# cerebellar_V1_2.net
KiCad netlist of a schematic drawn in EAGLE
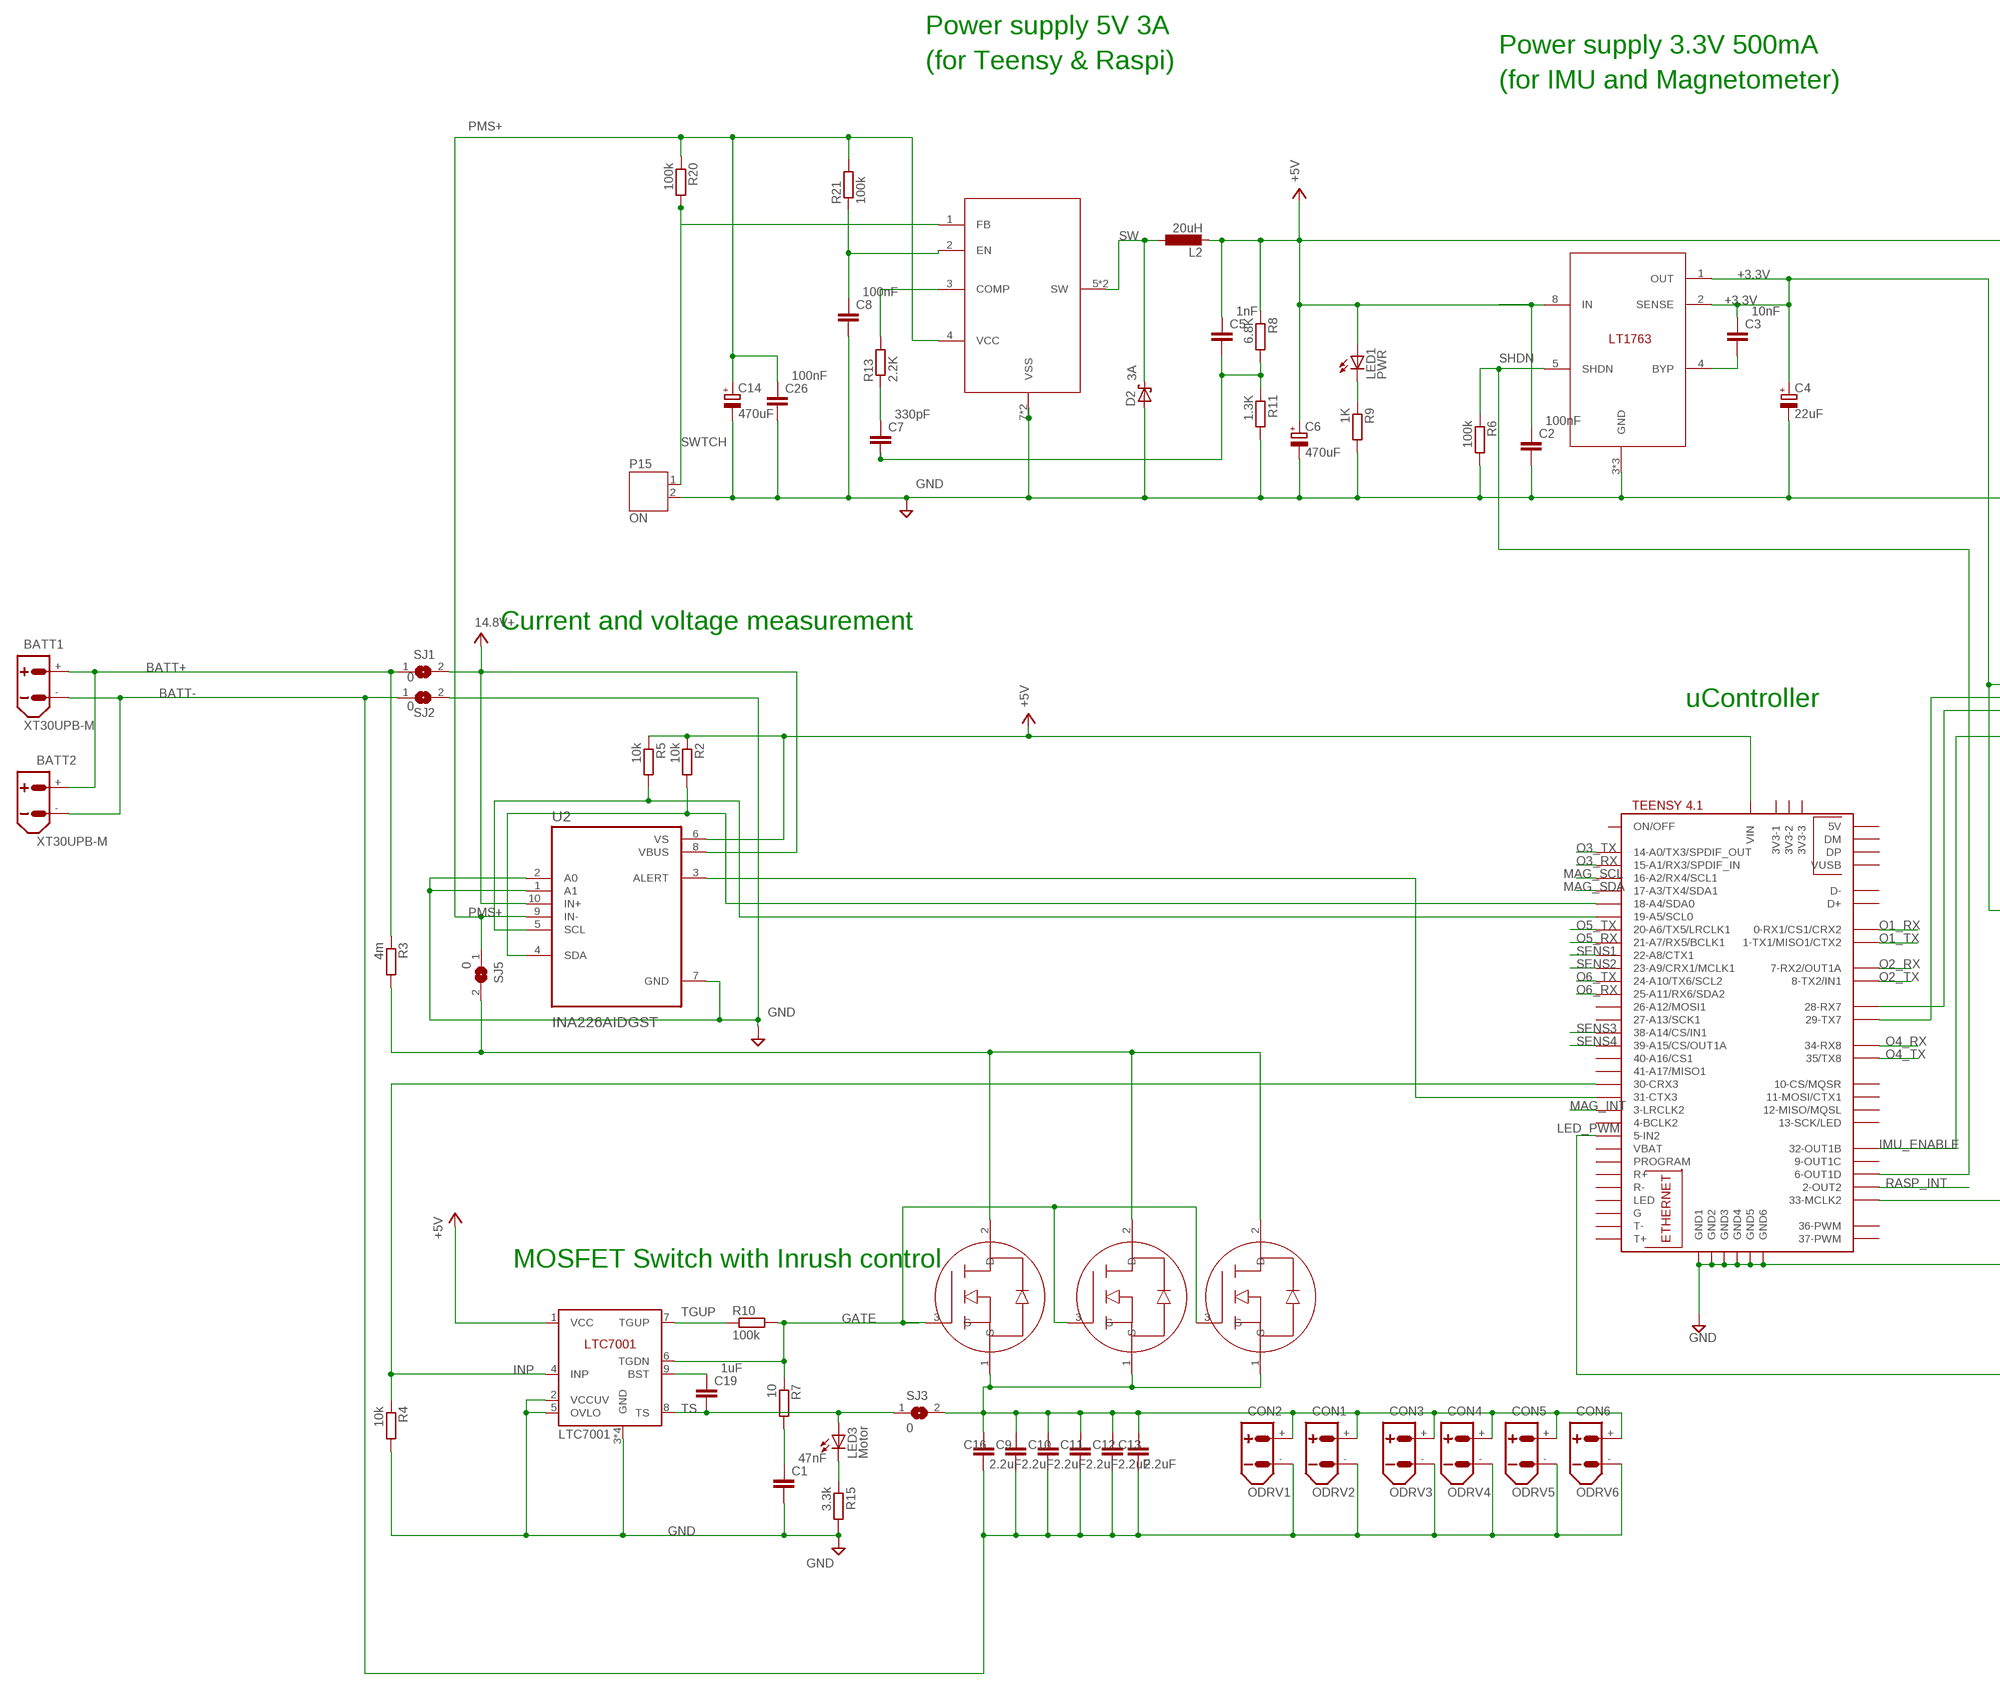
[diagram p0: schematic, sheet 1, part 1 of 2]
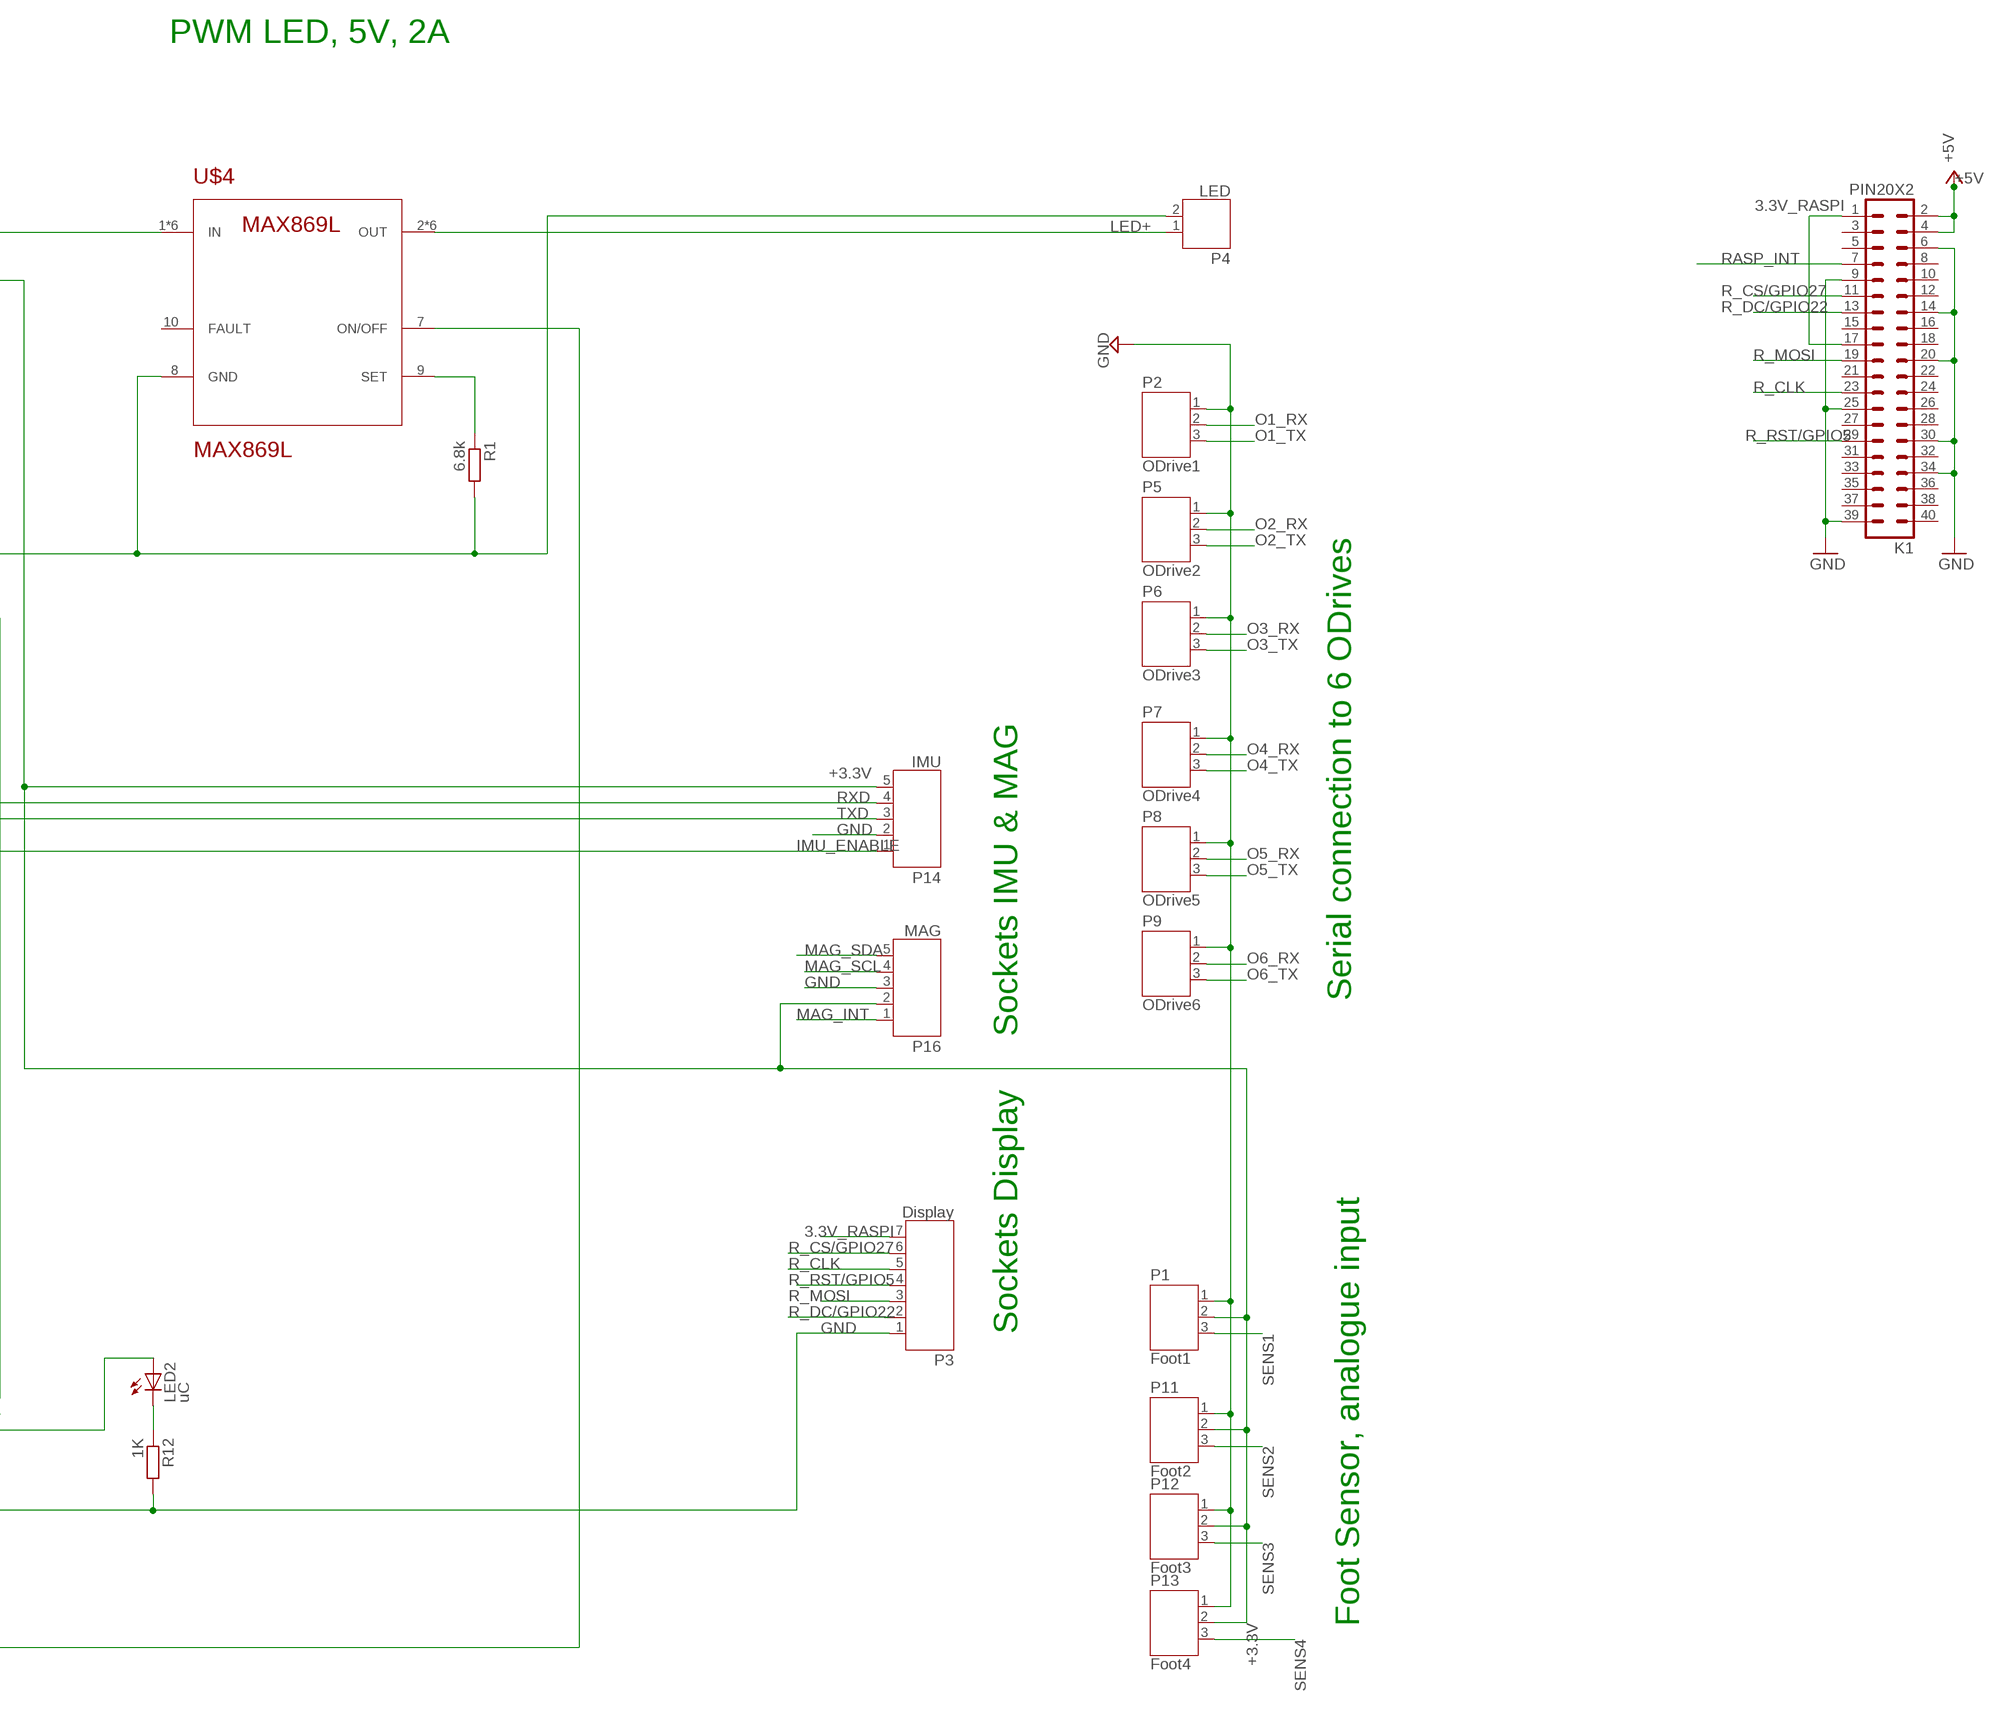
[diagram p1: schematic, sheet 1, part 2 of 2]

(export (version "E")
  (design (tool "Eeschema 10.0.6"))
  (components
    (comp (ref "BATT1")
      (value "XT30UPB-M")
      (footprint "eagle-import:XT30UPB-M")
      (libsource (lib "eagle-import") (part "XT30UPB-M"))
    )
    (comp (ref "BATT2")
      (value "XT30UPB-M")
      (footprint "eagle-import:XT30UPB-M")
      (libsource (lib "eagle-import") (part "XT30UPB-M"))
    )
    (comp (ref "C1")
      (value "47nF")
      (footprint "eagle-import:C050-024X044")
      (libsource (lib "eagle-import") (part "C-EU050-024X044"))
    )
    (comp (ref "C2")
      (value "100nF")
      (footprint "eagle-import:C050-024X044")
      (libsource (lib "eagle-import") (part "C-EU050-024X044"))
    )
    (comp (ref "C3")
      (value "10nF")
      (footprint "eagle-import:C050-024X044")
      (libsource (lib "eagle-import") (part "C-EU050-024X044"))
    )
    (comp (ref "C4")
      (value "22uF")
      (footprint "eagle-import:E2-4")
      (libsource (lib "eagle-import") (part "CPOL-EUE2-4"))
    )
    (comp (ref "C5")
      (value "1nF")
      (footprint "eagle-import:C050-024X044")
      (libsource (lib "eagle-import") (part "C-EU050-024X044"))
    )
    (comp (ref "C6")
      (value "470uF")
      (footprint "eagle-import:E2,5-6")
      (libsource (lib "eagle-import") (part "CPOL-EUE2.5-6"))
    )
    (comp (ref "C7")
      (value "330pF")
      (footprint "eagle-import:C050-024X044")
      (libsource (lib "eagle-import") (part "C-EU050-024X044"))
    )
    (comp (ref "C8")
      (value "100nF")
      (footprint "eagle-import:C050-024X044")
      (libsource (lib "eagle-import") (part "C-EU050-024X044"))
    )
    (comp (ref "C9")
      (value "2.2uF")
      (footprint "eagle-import:C050-024X044")
      (libsource (lib "eagle-import") (part "C-EU050-024X044"))
    )
    (comp (ref "C10")
      (value "2.2uF")
      (footprint "eagle-import:C050-024X044")
      (libsource (lib "eagle-import") (part "C-EU050-024X044"))
    )
    (comp (ref "C11")
      (value "2.2uF")
      (footprint "eagle-import:C050-024X044")
      (libsource (lib "eagle-import") (part "C-EU050-024X044"))
    )
    (comp (ref "C12")
      (value "2.2uF")
      (footprint "eagle-import:C050-024X044")
      (libsource (lib "eagle-import") (part "C-EU050-024X044"))
    )
    (comp (ref "C13")
      (value "2.2uF")
      (footprint "eagle-import:C050-024X044")
      (libsource (lib "eagle-import") (part "C-EU050-024X044"))
    )
    (comp (ref "C14")
      (value "470uF")
      (footprint "eagle-import:E2,5-6")
      (libsource (lib "eagle-import") (part "CPOL-EUE2.5-6"))
    )
    (comp (ref "C16")
      (value "2.2uF")
      (footprint "eagle-import:C050-024X044")
      (libsource (lib "eagle-import") (part "C-EU050-024X044"))
    )
    (comp (ref "C19")
      (value "1uF")
      (footprint "eagle-import:C050-024X044")
      (libsource (lib "eagle-import") (part "C-EU050-024X044"))
    )
    (comp (ref "C26")
      (value "100nF")
      (footprint "eagle-import:C050-024X044")
      (libsource (lib "eagle-import") (part "C-EU050-024X044"))
    )
    (comp (ref "CON1")
      (value "ODRV2")
      (footprint "eagle-import:XT30UPB-F")
      (libsource (lib "eagle-import") (part "XT30UPB-F"))
    )
    (comp (ref "CON2")
      (value "ODRV1")
      (footprint "eagle-import:XT30UPB-F")
      (libsource (lib "eagle-import") (part "XT30UPB-F"))
    )
    (comp (ref "CON3")
      (value "ODRV3")
      (footprint "eagle-import:XT30UPB-F")
      (libsource (lib "eagle-import") (part "XT30UPB-F"))
    )
    (comp (ref "CON4")
      (value "ODRV4")
      (footprint "eagle-import:XT30UPB-F")
      (libsource (lib "eagle-import") (part "XT30UPB-F"))
    )
    (comp (ref "CON5")
      (value "ODRV5")
      (footprint "eagle-import:XT30UPB-F")
      (libsource (lib "eagle-import") (part "XT30UPB-F"))
    )
    (comp (ref "CON6")
      (value "ODRV6")
      (footprint "eagle-import:XT30UPB-F")
      (libsource (lib "eagle-import") (part "XT30UPB-F"))
    )
    (comp (ref "D2")
      (value "3A")
      (footprint "eagle-import:DO41-10")
      (libsource (lib "eagle-import") (part "SCHOTTKY-DIODEDO41"))
    )
    (comp (ref "IC3")
      (value "LTC7001")
      (footprint "eagle-import:MSOP10")
      (fields (field (name "MPN") "AD7992BRMZ-0"))
      (libsource (lib "eagle-import") (part "LTC7001"))
    )
    (comp (ref "K1")
      (value "PIN20X2")
      (footprint "eagle-import:PIN_20X2")
      (libsource (lib "eagle-import") (part "PIN20X2"))
    )
    (comp (ref "L2")
      (value "20uH")
      (footprint "eagle-import:IRF-3")
      (libsource (lib "eagle-import") (part "L-EUIRF-3"))
    )
    (comp (ref "LED1")
      (value "PWR")
      (footprint "eagle-import:LED3MM")
      (libsource (lib "eagle-import") (part "LED3MM"))
    )
    (comp (ref "LED2")
      (value "uC")
      (footprint "eagle-import:LED3MM")
      (libsource (lib "eagle-import") (part "LED3MM"))
    )
    (comp (ref "LED3")
      (value "Motor")
      (footprint "eagle-import:LED3MM")
      (libsource (lib "eagle-import") (part "LED3MM"))
    )
    (comp (ref "P1")
      (value "Foot1")
      (footprint "eagle-import:JST-PH3")
      (libsource (lib "eagle-import") (part "JST-PH3"))
    )
    (comp (ref "P2")
      (value "ODrive1")
      (footprint "eagle-import:JST-PH3")
      (libsource (lib "eagle-import") (part "JST-PH3"))
    )
    (comp (ref "P3")
      (value "Display")
      (footprint "eagle-import:JST-PH7")
      (libsource (lib "eagle-import") (part "JST-PH7"))
    )
    (comp (ref "P4")
      (value "LED")
      (footprint "eagle-import:JST-PH2")
      (libsource (lib "eagle-import") (part "JST-PH2"))
    )
    (comp (ref "P5")
      (value "ODrive2")
      (footprint "eagle-import:JST-PH3")
      (libsource (lib "eagle-import") (part "JST-PH3"))
    )
    (comp (ref "P6")
      (value "ODrive3")
      (footprint "eagle-import:JST-PH3")
      (libsource (lib "eagle-import") (part "JST-PH3"))
    )
    (comp (ref "P7")
      (value "ODrive4")
      (footprint "eagle-import:JST-PH3")
      (libsource (lib "eagle-import") (part "JST-PH3"))
    )
    (comp (ref "P8")
      (value "ODrive5")
      (footprint "eagle-import:JST-PH3")
      (libsource (lib "eagle-import") (part "JST-PH3"))
    )
    (comp (ref "P9")
      (value "ODrive6")
      (footprint "eagle-import:JST-PH3")
      (libsource (lib "eagle-import") (part "JST-PH3"))
    )
    (comp (ref "P11")
      (value "Foot2")
      (footprint "eagle-import:JST-PH3")
      (libsource (lib "eagle-import") (part "JST-PH3"))
    )
    (comp (ref "P12")
      (value "Foot3")
      (footprint "eagle-import:JST-PH3")
      (libsource (lib "eagle-import") (part "JST-PH3"))
    )
    (comp (ref "P13")
      (value "Foot4")
      (footprint "eagle-import:JST-PH3")
      (libsource (lib "eagle-import") (part "JST-PH3"))
    )
    (comp (ref "P14")
      (value "IMU")
      (footprint "eagle-import:JST-PH5")
      (libsource (lib "eagle-import") (part "JST-PH5"))
    )
    (comp (ref "P15")
      (value "ON")
      (footprint "eagle-import:JST-PH2")
      (libsource (lib "eagle-import") (part "JST-PH2"))
    )
    (comp (ref "P16")
      (value "MAG")
      (footprint "eagle-import:JST-PH5")
      (libsource (lib "eagle-import") (part "JST-PH5"))
    )
    (comp (ref "R1")
      (value "6.8k")
      (footprint "eagle-import:0204_7")
      (libsource (lib "eagle-import") (part "R-EU_0204/7"))
    )
    (comp (ref "R2")
      (value "10k")
      (footprint "eagle-import:0204_7")
      (libsource (lib "eagle-import") (part "R-EU_0204/7"))
    )
    (comp (ref "R3")
      (value "4m")
      (footprint "eagle-import:R2512")
      (libsource (lib "eagle-import") (part "R-EU_R2512"))
    )
    (comp (ref "R4")
      (value "10k")
      (footprint "eagle-import:0204_7")
      (libsource (lib "eagle-import") (part "R-EU_0204/7"))
    )
    (comp (ref "R5")
      (value "10k")
      (footprint "eagle-import:0204_7")
      (libsource (lib "eagle-import") (part "R-EU_0204/7"))
    )
    (comp (ref "R6")
      (value "100k")
      (footprint "eagle-import:0204_7")
      (libsource (lib "eagle-import") (part "R-EU_0204/7"))
    )
    (comp (ref "R7")
      (value "10")
      (footprint "eagle-import:0204_7")
      (libsource (lib "eagle-import") (part "R-EU_0204/7"))
    )
    (comp (ref "R8")
      (value "6.8K")
      (footprint "eagle-import:0204_7")
      (libsource (lib "eagle-import") (part "R-EU_0204/7"))
    )
    (comp (ref "R9")
      (value "1K")
      (footprint "eagle-import:0204_7")
      (libsource (lib "eagle-import") (part "R-EU_0204/7"))
    )
    (comp (ref "R10")
      (value "100k")
      (footprint "eagle-import:0204_7")
      (libsource (lib "eagle-import") (part "R-EU_0204/7"))
    )
    (comp (ref "R11")
      (value "1.3K")
      (footprint "eagle-import:0204_7")
      (libsource (lib "eagle-import") (part "R-EU_0204/7"))
    )
    (comp (ref "R12")
      (value "1K")
      (footprint "eagle-import:0204_7")
      (libsource (lib "eagle-import") (part "R-EU_0204/7"))
    )
    (comp (ref "R13")
      (value "2.2K")
      (footprint "eagle-import:0204_7")
      (libsource (lib "eagle-import") (part "R-EU_0204/7"))
    )
    (comp (ref "R15")
      (value "3.3k")
      (footprint "eagle-import:0204_7")
      (libsource (lib "eagle-import") (part "R-EU_0204/7"))
    )
    (comp (ref "R20")
      (value "100k")
      (footprint "eagle-import:0204_7")
      (libsource (lib "eagle-import") (part "R-EU_0204/7"))
    )
    (comp (ref "R21")
      (value "100k")
      (footprint "eagle-import:0204_7")
      (libsource (lib "eagle-import") (part "R-EU_0204/7"))
    )
    (comp (ref "SJ1") (value "0") (footprint "eagle-import:SJ") (libsource (lib "eagle-import") (part "SJ")))
    (comp (ref "SJ2") (value "0") (footprint "eagle-import:SJ") (libsource (lib "eagle-import") (part "SJ")))
    (comp (ref "SJ3") (value "0") (footprint "eagle-import:SJ") (libsource (lib "eagle-import") (part "SJ")))
    (comp (ref "SJ5") (value "0") (footprint "eagle-import:SJ") (libsource (lib "eagle-import") (part "SJ")))
    (comp (ref "U$1")
      (value "TEENSY41")
      (footprint "eagle-import:TEENSY41")
      (libsource (lib "eagle-import") (part "TEENSY41"))
    )
    (comp (ref "U$2")
      (value "IRF2804-BACK")
      (footprint "eagle-import:TO-220H-BACK")
      (libsource (lib "eagle-import") (part "IRF2804-BACK"))
    )
    (comp (ref "U$3")
      (value "IRF2804-BACK")
      (footprint "eagle-import:TO-220H-BACK")
      (libsource (lib "eagle-import") (part "IRF2804-BACK"))
    )
    (comp (ref "U$4")
      (value "MAX869L")
      (footprint "eagle-import:TSSOP-16")
      (libsource (lib "eagle-import") (part "MAX769L"))
    )
    (comp (ref "U$5")
      (value "IRF2804-BACK")
      (footprint "eagle-import:TO-220H-BACK")
      (libsource (lib "eagle-import") (part "IRF2804-BACK"))
    )
    (comp (ref "U$6")
      (value "TS2509")
      (footprint "eagle-import:SO08")
      (libsource (lib "eagle-import") (part "TS2509"))
    )
    (comp (ref "U$8")
      (value "LT1763")
      (footprint "eagle-import:SO08")
      (libsource (lib "eagle-import") (part "LT1763"))
    )
    (comp (ref "U2")
      (value "INA226AIDGST")
      (footprint "eagle-import:SOP50P490X110-10N")
      (fields (field (name "MF") "Texas Instruments"))
      (libsource (lib "eagle-import") (part "INA226AIDGST"))
    )
  )
  (nets
    (net (code "1") (name "+5V") (class "Default")
      (node (ref "C2") (pin "1") (pinfunction "1_1") (pintype "passive"))
      (node (ref "C5") (pin "1") (pinfunction "1_1") (pintype "passive"))
      (node (ref "C6") (pin "+") (pinfunction "+_+") (pintype "passive"))
      (node (ref "IC3") (pin "1") (pinfunction "VCC_1") (pintype "power_in"))
      (node (ref "K1") (pin "2") (pinfunction "2_2") (pintype "passive"))
      (node (ref "K1") (pin "4") (pinfunction "4_4") (pintype "passive"))
      (node (ref "L2") (pin "2") (pinfunction "2_2") (pintype "passive"))
      (node (ref "LED1") (pin "A") (pinfunction "A_A") (pintype "passive"))
      (node (ref "R2") (pin "1") (pinfunction "1_1") (pintype "passive"))
      (node (ref "R5") (pin "1") (pinfunction "1_1") (pintype "passive"))
      (node (ref "R8") (pin "1") (pinfunction "1_1") (pintype "passive"))
      (node (ref "U$1") (pin "VIN") (pinfunction "VIN_VIN") (pintype "bidirectional"))
      (node (ref "U$4") (pin "1") (pinfunction "IN_1") (pintype "bidirectional"))
      (node (ref "U$4") (pin "12") (pinfunction "IN_12") (pintype "bidirectional"))
      (node (ref "U$4") (pin "13") (pinfunction "IN_13") (pintype "bidirectional"))
      (node (ref "U$4") (pin "16") (pinfunction "IN_16") (pintype "bidirectional"))
      (node (ref "U$4") (pin "4") (pinfunction "IN_4") (pintype "bidirectional"))
      (node (ref "U$4") (pin "5") (pinfunction "IN_5") (pintype "bidirectional"))
      (node (ref "U$8") (pin "8") (pinfunction "IN_8") (pintype "input"))
      (node (ref "U2") (pin "6") (pinfunction "VS_6") (pintype "power_in"))
    )
    (net (code "2") (name "/+3.3V") (class "Default")
      (node (ref "C3") (pin "1") (pinfunction "1_1") (pintype "passive"))
      (node (ref "C4") (pin "+") (pinfunction "+_+") (pintype "passive"))
      (node (ref "P1") (pin "2") (pinfunction "2_2") (pintype "passive"))
      (node (ref "P11") (pin "2") (pinfunction "2_2") (pintype "passive"))
      (node (ref "P12") (pin "2") (pinfunction "2_2") (pintype "passive"))
      (node (ref "P13") (pin "2") (pinfunction "2_2") (pintype "passive"))
      (node (ref "P14") (pin "5") (pinfunction "5_5") (pintype "passive"))
      (node (ref "P16") (pin "2") (pinfunction "2_2") (pintype "passive"))
      (node (ref "U$8") (pin "1") (pinfunction "OUT_1") (pintype "output"))
      (node (ref "U$8") (pin "2") (pinfunction "SENSE_2") (pintype "input"))
    )
    (net (code "3") (name "/3.3V_RASPI") (class "Default")
      (node (ref "K1") (pin "1") (pinfunction "1_1") (pintype "passive"))
      (node (ref "K1") (pin "17") (pinfunction "17_17") (pintype "passive"))
      (node (ref "P3") (pin "7") (pinfunction "7_7") (pintype "passive"))
    )
    (net (code "4") (name "/BATT+") (class "Default")
      (node (ref "BATT1") (pin "+") (pinfunction "+_+") (pintype "power_in"))
      (node (ref "BATT2") (pin "+") (pinfunction "+_+") (pintype "power_in"))
      (node (ref "R3") (pin "1") (pinfunction "1_1") (pintype "passive"))
      (node (ref "SJ1") (pin "1") (pinfunction "1_1") (pintype "passive"))
    )
    (net (code "5") (name "/BATT-") (class "Default")
      (node (ref "BATT1") (pin "-") (pinfunction "-_-") (pintype "power_in"))
      (node (ref "BATT2") (pin "-") (pinfunction "-_-") (pintype "power_in"))
      (node (ref "C10") (pin "2") (pinfunction "2_2") (pintype "passive"))
      (node (ref "C11") (pin "2") (pinfunction "2_2") (pintype "passive"))
      (node (ref "C12") (pin "2") (pinfunction "2_2") (pintype "passive"))
      (node (ref "C13") (pin "2") (pinfunction "2_2") (pintype "passive"))
      (node (ref "C16") (pin "2") (pinfunction "2_2") (pintype "passive"))
      (node (ref "C9") (pin "2") (pinfunction "2_2") (pintype "passive"))
      (node (ref "CON1") (pin "-") (pinfunction "-_-") (pintype "power_in"))
      (node (ref "CON2") (pin "-") (pinfunction "-_-") (pintype "power_in"))
      (node (ref "CON3") (pin "-") (pinfunction "-_-") (pintype "power_in"))
      (node (ref "CON4") (pin "-") (pinfunction "-_-") (pintype "power_in"))
      (node (ref "CON5") (pin "-") (pinfunction "-_-") (pintype "power_in"))
      (node (ref "CON6") (pin "-") (pinfunction "-_-") (pintype "power_in"))
      (node (ref "SJ2") (pin "1") (pinfunction "1_1") (pintype "passive"))
    )
    (net (code "6") (name "/GATE") (class "Default")
      (node (ref "IC3") (pin "6") (pinfunction "TGDN_6") (pintype "output"))
      (node (ref "R10") (pin "2") (pinfunction "2_2") (pintype "passive"))
      (node (ref "R7") (pin "1") (pinfunction "1_1") (pintype "passive"))
      (node (ref "U$2") (pin "3") (pinfunction "G_3") (pintype "bidirectional"))
      (node (ref "U$3") (pin "3") (pinfunction "G_3") (pintype "bidirectional"))
      (node (ref "U$5") (pin "3") (pinfunction "G_3") (pintype "bidirectional"))
    )
    (net (code "7") (name "/IMU_ENABLE") (class "Default")
      (node (ref "P14") (pin "1") (pinfunction "1_1") (pintype "passive"))
      (node (ref "U$1") (pin "32-OUT1B") (pinfunction "32-OUT1B_32-OUT1B") (pintype "bidirectional"))
    )
    (net (code "8") (name "/INP") (class "Default")
      (node (ref "IC3") (pin "4") (pinfunction "INP_4") (pintype "input"))
      (node (ref "R4") (pin "1") (pinfunction "1_1") (pintype "passive"))
      (node (ref "U$1") (pin "30-CRX3") (pinfunction "30-CRX3_30-CRX3") (pintype "bidirectional"))
    )
    (net (code "9") (name "/LED+") (class "Default")
      (node (ref "P4") (pin "1") (pinfunction "1_1") (pintype "passive"))
      (node (ref "U$4") (pin "11") (pinfunction "OUT_11") (pintype "bidirectional"))
      (node (ref "U$4") (pin "14") (pinfunction "OUT_14") (pintype "bidirectional"))
      (node (ref "U$4") (pin "15") (pinfunction "OUT_15") (pintype "bidirectional"))
      (node (ref "U$4") (pin "2") (pinfunction "OUT_2") (pintype "bidirectional"))
      (node (ref "U$4") (pin "3") (pinfunction "OUT_3") (pintype "bidirectional"))
      (node (ref "U$4") (pin "6") (pinfunction "OUT_6") (pintype "bidirectional"))
    )
    (net (code "10") (name "/LED_PWM") (class "Default")
      (node (ref "U$1") (pin "5-IN2") (pinfunction "5-IN2_5-IN2") (pintype "bidirectional"))
      (node (ref "U$4") (pin "7") (pinfunction "ON/OFF_7") (pintype "bidirectional"))
    )
    (net (code "11") (name "/MAG_INT") (class "Default")
      (node (ref "P16") (pin "1") (pinfunction "1_1") (pintype "passive"))
      (node (ref "U$1") (pin "3-LRCLK2") (pinfunction "3-LRCLK2_3-LRCLK2") (pintype "bidirectional"))
    )
    (net (code "12") (name "/MAG_SCL") (class "Default")
      (node (ref "P16") (pin "4") (pinfunction "4_4") (pintype "passive"))
      (node (ref "U$1") (pin "16-A2/RX4/SCL1") (pinfunction "16-A2/RX4/SCL1_16-A2/RX4/SCL1") (pintype "bidirectional"))
    )
    (net (code "13") (name "/MAG_SDA") (class "Default")
      (node (ref "P16") (pin "5") (pinfunction "5_5") (pintype "passive"))
      (node (ref "U$1") (pin "17-A3/TX4/SDA1") (pinfunction "17-A3/TX4/SDA1_17-A3/TX4/SDA1") (pintype "bidirectional"))
    )
    (net (code "14") (name "/O1_RX") (class "Default")
      (node (ref "P2") (pin "2") (pinfunction "2_2") (pintype "passive"))
      (node (ref "U$1") (pin "0-RX1/CS1/CRX2") (pinfunction "0-RX1/CS1/CRX2_0-RX1/CS1/CRX2") (pintype "bidirectional"))
    )
    (net (code "15") (name "/O1_TX") (class "Default")
      (node (ref "P2") (pin "3") (pinfunction "3_3") (pintype "passive"))
      (node (ref "U$1") (pin "1-TX1/MISO1/CTX2") (pinfunction "1-TX1/MISO1/CTX2_1-TX1/MISO1/CTX2") (pintype "bidirectional"))
    )
    (net (code "16") (name "/O2_RX") (class "Default")
      (node (ref "P5") (pin "2") (pinfunction "2_2") (pintype "passive"))
      (node (ref "U$1") (pin "7-RX2/OUT1A") (pinfunction "7-RX2/OUT1A_7-RX2/OUT1A") (pintype "bidirectional"))
    )
    (net (code "17") (name "/O2_TX") (class "Default")
      (node (ref "P5") (pin "3") (pinfunction "3_3") (pintype "passive"))
      (node (ref "U$1") (pin "8-TX2/IN1") (pinfunction "8-TX2/IN1_8-TX2/IN1") (pintype "bidirectional"))
    )
    (net (code "18") (name "/O3_RX") (class "Default")
      (node (ref "P6") (pin "2") (pinfunction "2_2") (pintype "passive"))
      (node (ref "U$1") (pin "15-A1/RX3/SPDIF_IN") (pinfunction "15-A1/RX3/SPDIF_IN_15-A1/RX3/SPDIF_IN") (pintype "bidirectional"))
    )
    (net (code "19") (name "/O3_TX") (class "Default")
      (node (ref "P6") (pin "3") (pinfunction "3_3") (pintype "passive"))
      (node (ref "U$1") (pin "14-A0/TX3/SPDIF_OUT") (pinfunction "14-A0/TX3/SPDIF_OUT_14-A0/TX3/SPDIF_OUT") (pintype "bidirectional"))
    )
    (net (code "20") (name "/O4_RX") (class "Default")
      (node (ref "P7") (pin "2") (pinfunction "2_2") (pintype "passive"))
      (node (ref "U$1") (pin "34-RX8") (pinfunction "34-RX8_34-RX8") (pintype "bidirectional"))
    )
    (net (code "21") (name "/O4_TX") (class "Default")
      (node (ref "P7") (pin "3") (pinfunction "3_3") (pintype "passive"))
      (node (ref "U$1") (pin "35-TX8") (pinfunction "35/TX8_35-TX8") (pintype "bidirectional"))
    )
    (net (code "22") (name "/O5_RX") (class "Default")
      (node (ref "P8") (pin "2") (pinfunction "2_2") (pintype "passive"))
      (node (ref "U$1") (pin "21-A7/RX5/BCLK1") (pinfunction "21-A7/RX5/BCLK1_21-A7/RX5/BCLK1") (pintype "bidirectional"))
    )
    (net (code "23") (name "/O5_TX") (class "Default")
      (node (ref "P8") (pin "3") (pinfunction "3_3") (pintype "passive"))
      (node (ref "U$1") (pin "20-A6/TX5/LRCLK1") (pinfunction "20-A6/TX5/LRCLK1_20-A6/TX5/LRCLK1") (pintype "bidirectional"))
    )
    (net (code "24") (name "/O6_RX") (class "Default")
      (node (ref "P9") (pin "2") (pinfunction "2_2") (pintype "passive"))
      (node (ref "U$1") (pin "25-A11/RX6/SDA2") (pinfunction "25-A11/RX6/SDA2_25-A11/RX6/SDA2") (pintype "bidirectional"))
    )
    (net (code "25") (name "/O6_TX") (class "Default")
      (node (ref "P9") (pin "3") (pinfunction "3_3") (pintype "passive"))
      (node (ref "U$1") (pin "24-A10/TX6/SCL2") (pinfunction "24-A10/TX6/SCL2_24-A10/TX6/SCL2") (pintype "bidirectional"))
    )
    (net (code "26") (name "/PMS+") (class "Default")
      (node (ref "C14") (pin "+") (pinfunction "+_+") (pintype "passive"))
      (node (ref "C26") (pin "1") (pinfunction "1_1") (pintype "passive"))
      (node (ref "R20") (pin "1") (pinfunction "1_1") (pintype "passive"))
      (node (ref "R21") (pin "2") (pinfunction "2_2") (pintype "passive"))
      (node (ref "SJ5") (pin "1") (pinfunction "1_1") (pintype "passive"))
      (node (ref "U$6") (pin "4") (pinfunction "VCC_4") (pintype "input"))
      (node (ref "U2") (pin "9") (pinfunction "IN-_9") (pintype "input"))
    )
    (net (code "27") (name "/RASP_INT") (class "Default")
      (node (ref "K1") (pin "7") (pinfunction "7_7") (pintype "passive"))
      (node (ref "U$1") (pin "2-OUT2") (pinfunction "2-OUT2_2-OUT2") (pintype "bidirectional"))
    )
    (net (code "28") (name "/RXD") (class "Default")
      (node (ref "P14") (pin "4") (pinfunction "4_4") (pintype "passive"))
      (node (ref "U$1") (pin "29-TX7") (pinfunction "29-TX7_29-TX7") (pintype "bidirectional"))
    )
    (net (code "29") (name "/R_CLK") (class "Default")
      (node (ref "K1") (pin "23") (pinfunction "23_23") (pintype "passive"))
      (node (ref "P3") (pin "5") (pinfunction "5_5") (pintype "passive"))
    )
    (net (code "30") (name "/R_CS{slash}GPIO27") (class "Default")
      (node (ref "K1") (pin "11") (pinfunction "11_11") (pintype "passive"))
      (node (ref "P3") (pin "6") (pinfunction "6_6") (pintype "passive"))
    )
    (net (code "31") (name "/R_DC{slash}GPIO22") (class "Default")
      (node (ref "K1") (pin "13") (pinfunction "13_13") (pintype "passive"))
      (node (ref "P3") (pin "2") (pinfunction "2_2") (pintype "passive"))
    )
    (net (code "32") (name "/R_MOSI") (class "Default")
      (node (ref "K1") (pin "19") (pinfunction "19_19") (pintype "passive"))
      (node (ref "P3") (pin "3") (pinfunction "3_3") (pintype "passive"))
    )
    (net (code "33") (name "/R_RST{slash}GPIO5") (class "Default")
      (node (ref "K1") (pin "29") (pinfunction "29_29") (pintype "passive"))
      (node (ref "P3") (pin "4") (pinfunction "4_4") (pintype "passive"))
    )
    (net (code "34") (name "/SENS1") (class "Default")
      (node (ref "P1") (pin "3") (pinfunction "3_3") (pintype "passive"))
      (node (ref "U$1") (pin "22-A8/CTX1") (pinfunction "22-A8/CTX1_22-A8/CTX1") (pintype "bidirectional"))
    )
    (net (code "35") (name "/SENS2") (class "Default")
      (node (ref "P11") (pin "3") (pinfunction "3_3") (pintype "passive"))
      (node (ref "U$1") (pin "23-A9/CRX1/MCLK1") (pinfunction "23-A9/CRX1/MCLK1_23-A9/CRX1/MCLK1") (pintype "bidirectional"))
    )
    (net (code "36") (name "/SENS3") (class "Default")
      (node (ref "P12") (pin "3") (pinfunction "3_3") (pintype "passive"))
      (node (ref "U$1") (pin "38-A14/CS/IN1") (pinfunction "38-A14/CS/IN1_38-A14/CS/IN1") (pintype "bidirectional"))
    )
    (net (code "37") (name "/SENS4") (class "Default")
      (node (ref "P13") (pin "3") (pinfunction "3_3") (pintype "passive"))
      (node (ref "U$1") (pin "39-A15/CS/OUT1A") (pinfunction "39-A15/CS/OUT1A_39-A15/CS/OUT1A") (pintype "bidirectional"))
    )
    (net (code "38") (name "/SHDN") (class "Default")
      (node (ref "R6") (pin "1") (pinfunction "1_1") (pintype "passive"))
      (node (ref "U$1") (pin "6-OUT1D") (pinfunction "6-OUT1D_6-OUT1D") (pintype "bidirectional"))
      (node (ref "U$8") (pin "5") (pinfunction "SHDN_5") (pintype "bidirectional"))
    )
    (net (code "39") (name "/SW") (class "Default")
      (node (ref "D2") (pin "C") (pinfunction "C_C") (pintype "passive"))
      (node (ref "L2") (pin "1") (pinfunction "1_1") (pintype "passive"))
      (node (ref "U$6") (pin "5") (pinfunction "SW_5") (pintype "output"))
      (node (ref "U$6") (pin "6") (pinfunction "SW_6") (pintype "output"))
    )
    (net (code "40") (name "/SWTCH") (class "Default")
      (node (ref "P15") (pin "1") (pinfunction "1_1") (pintype "passive"))
      (node (ref "R20") (pin "2") (pinfunction "2_2") (pintype "passive"))
      (node (ref "U$6") (pin "1") (pinfunction "FB_1") (pintype "bidirectional"))
    )
    (net (code "41") (name "/TGUP") (class "Default")
      (node (ref "IC3") (pin "7") (pinfunction "TGUP_7") (pintype "input"))
      (node (ref "R10") (pin "1") (pinfunction "1_1") (pintype "passive"))
    )
    (net (code "42") (name "/TS") (class "Default")
      (node (ref "C19") (pin "2") (pinfunction "2_2") (pintype "passive"))
      (node (ref "IC3") (pin "8") (pinfunction "TS_8") (pintype "bidirectional"))
      (node (ref "LED3") (pin "A") (pinfunction "A_A") (pintype "passive"))
      (node (ref "SJ3") (pin "1") (pinfunction "1_1") (pintype "passive"))
    )
    (net (code "43") (name "/TXD") (class "Default")
      (node (ref "P14") (pin "3") (pinfunction "3_3") (pintype "passive"))
      (node (ref "U$1") (pin "28-RX7") (pinfunction "28-RX7_28-RX7") (pintype "bidirectional"))
    )
    (net (code "44") (name "14.8V+") (class "Default")
      (node (ref "SJ1") (pin "2") (pinfunction "2_2") (pintype "passive"))
      (node (ref "U2") (pin "10") (pinfunction "IN+_10") (pintype "input"))
      (node (ref "U2") (pin "8") (pinfunction "VBUS_8") (pintype "power_in"))
    )
    (net (code "45") (name "GND") (class "Default")
      (node (ref "C1") (pin "2") (pinfunction "2_2") (pintype "passive"))
      (node (ref "C14") (pin "-") (pinfunction "-_-") (pintype "passive"))
      (node (ref "C2") (pin "2") (pinfunction "2_2") (pintype "passive"))
      (node (ref "C26") (pin "2") (pinfunction "2_2") (pintype "passive"))
      (node (ref "C4") (pin "-") (pinfunction "-_-") (pintype "passive"))
      (node (ref "C6") (pin "-") (pinfunction "-_-") (pintype "passive"))
      (node (ref "C8") (pin "2") (pinfunction "2_2") (pintype "passive"))
      (node (ref "D2") (pin "A") (pinfunction "A_A") (pintype "passive"))
      (node (ref "IC3") (pin "10") (pinfunction "GND_10") (pintype "power_in"))
      (node (ref "IC3") (pin "11") (pinfunction "GND_11") (pintype "power_in"))
      (node (ref "IC3") (pin "12") (pinfunction "GND_12") (pintype "power_in"))
      (node (ref "IC3") (pin "2") (pinfunction "VCCUV_2") (pintype "input"))
      (node (ref "IC3") (pin "3") (pinfunction "GND_3") (pintype "power_in"))
      (node (ref "IC3") (pin "5") (pinfunction "OVLO_5") (pintype "input"))
      (node (ref "K1") (pin "14") (pinfunction "14_14") (pintype "passive"))
      (node (ref "K1") (pin "20") (pinfunction "20_20") (pintype "passive"))
      (node (ref "K1") (pin "25") (pinfunction "25_25") (pintype "passive"))
      (node (ref "K1") (pin "30") (pinfunction "30_30") (pintype "passive"))
      (node (ref "K1") (pin "34") (pinfunction "34_34") (pintype "passive"))
      (node (ref "K1") (pin "39") (pinfunction "39_39") (pintype "passive"))
      (node (ref "K1") (pin "6") (pinfunction "6_6") (pintype "passive"))
      (node (ref "K1") (pin "9") (pinfunction "9_9") (pintype "passive"))
      (node (ref "P1") (pin "1") (pinfunction "1_1") (pintype "passive"))
      (node (ref "P11") (pin "1") (pinfunction "1_1") (pintype "passive"))
      (node (ref "P12") (pin "1") (pinfunction "1_1") (pintype "passive"))
      (node (ref "P13") (pin "1") (pinfunction "1_1") (pintype "passive"))
      (node (ref "P14") (pin "2") (pinfunction "2_2") (pintype "passive"))
      (node (ref "P15") (pin "2") (pinfunction "2_2") (pintype "passive"))
      (node (ref "P16") (pin "3") (pinfunction "3_3") (pintype "passive"))
      (node (ref "P2") (pin "1") (pinfunction "1_1") (pintype "passive"))
      (node (ref "P3") (pin "1") (pinfunction "1_1") (pintype "passive"))
      (node (ref "P4") (pin "2") (pinfunction "2_2") (pintype "passive"))
      (node (ref "P5") (pin "1") (pinfunction "1_1") (pintype "passive"))
      (node (ref "P6") (pin "1") (pinfunction "1_1") (pintype "passive"))
      (node (ref "P7") (pin "1") (pinfunction "1_1") (pintype "passive"))
      (node (ref "P8") (pin "1") (pinfunction "1_1") (pintype "passive"))
      (node (ref "P9") (pin "1") (pinfunction "1_1") (pintype "passive"))
      (node (ref "R1") (pin "2") (pinfunction "2_2") (pintype "passive"))
      (node (ref "R11") (pin "2") (pinfunction "2_2") (pintype "passive"))
      (node (ref "R12") (pin "2") (pinfunction "2_2") (pintype "passive"))
      (node (ref "R15") (pin "2") (pinfunction "2_2") (pintype "passive"))
      (node (ref "R4") (pin "2") (pinfunction "2_2") (pintype "passive"))
      (node (ref "R6") (pin "2") (pinfunction "2_2") (pintype "passive"))
      (node (ref "R9") (pin "2") (pinfunction "2_2") (pintype "passive"))
      (node (ref "SJ2") (pin "2") (pinfunction "2_2") (pintype "passive"))
      (node (ref "U$1") (pin "GND1") (pinfunction "GND1_GND1") (pintype "bidirectional"))
      (node (ref "U$1") (pin "GND2") (pinfunction "GND2_GND2") (pintype "bidirectional"))
      (node (ref "U$1") (pin "GND3") (pinfunction "GND3_GND3") (pintype "bidirectional"))
      (node (ref "U$1") (pin "GND4") (pinfunction "GND4_GND4") (pintype "bidirectional"))
      (node (ref "U$1") (pin "GND5") (pinfunction "GND5_GND5") (pintype "bidirectional"))
      (node (ref "U$1") (pin "GND6") (pinfunction "GND6_GND6") (pintype "bidirectional"))
      (node (ref "U$4") (pin "8") (pinfunction "GND_8") (pintype "bidirectional"))
      (node (ref "U$6") (pin "7") (pinfunction "VSS_7") (pintype "input"))
      (node (ref "U$6") (pin "8") (pinfunction "VSS_8") (pintype "input"))
      (node (ref "U$8") (pin "3") (pinfunction "GND_3") (pintype "bidirectional"))
      (node (ref "U$8") (pin "6") (pinfunction "GND_6") (pintype "bidirectional"))
      (node (ref "U$8") (pin "7") (pinfunction "GND_7") (pintype "bidirectional"))
      (node (ref "U2") (pin "1") (pinfunction "A1_1") (pintype "input"))
      (node (ref "U2") (pin "2") (pinfunction "A0_2") (pintype "input"))
      (node (ref "U2") (pin "7") (pinfunction "GND_7") (pintype "power_in"))
    )
    (net (code "46") (name "Net-(C1-Pad1)") (class "Default")
      (node (ref "C1") (pin "1") (pinfunction "1_1") (pintype "passive"))
      (node (ref "R7") (pin "2") (pinfunction "2_2") (pintype "passive"))
    )
    (net (code "47") (name "Net-(C5-Pad2)") (class "Default")
      (node (ref "C5") (pin "2") (pinfunction "2_2") (pintype "passive"))
      (node (ref "C7") (pin "2") (pinfunction "2_2") (pintype "passive"))
      (node (ref "R11") (pin "1") (pinfunction "1_1") (pintype "passive"))
      (node (ref "R8") (pin "2") (pinfunction "2_2") (pintype "passive"))
    )
    (net (code "48") (name "Net-(C7-Pad1)") (class "Default")
      (node (ref "C7") (pin "1") (pinfunction "1_1") (pintype "passive"))
      (node (ref "R13") (pin "1") (pinfunction "1_1") (pintype "passive"))
    )
    (net (code "49") (name "Net-(IC3-BST)") (class "Default")
      (node (ref "C19") (pin "1") (pinfunction "1_1") (pintype "passive"))
      (node (ref "IC3") (pin "9") (pinfunction "BST_9") (pintype "input"))
    )
    (net (code "50") (name "Net-(LED1-C)") (class "Default")
      (node (ref "LED1") (pin "K") (pinfunction "C_K") (pintype "passive"))
      (node (ref "R9") (pin "1") (pinfunction "1_1") (pintype "passive"))
    )
    (net (code "51") (name "Net-(LED2-C)") (class "Default")
      (node (ref "LED2") (pin "K") (pinfunction "C_K") (pintype "passive"))
      (node (ref "R12") (pin "1") (pinfunction "1_1") (pintype "passive"))
    )
    (net (code "52") (name "Net-(LED2-PadA)") (class "Default")
      (node (ref "LED2") (pin "A") (pinfunction "A_A") (pintype "passive"))
      (node (ref "U$1") (pin "33-MCLK2") (pinfunction "33-MCLK2_33-MCLK2") (pintype "bidirectional"))
    )
    (net (code "53") (name "Net-(LED3-C)") (class "Default")
      (node (ref "LED3") (pin "K") (pinfunction "C_K") (pintype "passive"))
      (node (ref "R15") (pin "1") (pinfunction "1_1") (pintype "passive"))
    )
    (net (code "54") (name "Net-(U$2-D)") (class "Default")
      (node (ref "R3") (pin "2") (pinfunction "2_2") (pintype "passive"))
      (node (ref "SJ5") (pin "2") (pinfunction "2_2") (pintype "passive"))
      (node (ref "U$2") (pin "2") (pinfunction "D_2") (pintype "bidirectional"))
      (node (ref "U$3") (pin "2") (pinfunction "D_2") (pintype "bidirectional"))
      (node (ref "U$5") (pin "2") (pinfunction "D_2") (pintype "bidirectional"))
    )
    (net (code "55") (name "Net-(U$2-S)") (class "Default")
      (node (ref "C10") (pin "1") (pinfunction "1_1") (pintype "passive"))
      (node (ref "C11") (pin "1") (pinfunction "1_1") (pintype "passive"))
      (node (ref "C12") (pin "1") (pinfunction "1_1") (pintype "passive"))
      (node (ref "C13") (pin "1") (pinfunction "1_1") (pintype "passive"))
      (node (ref "C16") (pin "1") (pinfunction "1_1") (pintype "passive"))
      (node (ref "C9") (pin "1") (pinfunction "1_1") (pintype "passive"))
      (node (ref "CON1") (pin "+") (pinfunction "+_+") (pintype "power_in"))
      (node (ref "CON2") (pin "+") (pinfunction "+_+") (pintype "power_in"))
      (node (ref "CON3") (pin "+") (pinfunction "+_+") (pintype "power_in"))
      (node (ref "CON4") (pin "+") (pinfunction "+_+") (pintype "power_in"))
      (node (ref "CON5") (pin "+") (pinfunction "+_+") (pintype "power_in"))
      (node (ref "CON6") (pin "+") (pinfunction "+_+") (pintype "power_in"))
      (node (ref "SJ3") (pin "2") (pinfunction "2_2") (pintype "passive"))
      (node (ref "U$2") (pin "1") (pinfunction "S_1") (pintype "bidirectional"))
      (node (ref "U$3") (pin "1") (pinfunction "S_1") (pintype "bidirectional"))
      (node (ref "U$5") (pin "1") (pinfunction "S_1") (pintype "bidirectional"))
    )
    (net (code "56") (name "Net-(U$4-SET)") (class "Default")
      (node (ref "R1") (pin "1") (pinfunction "1_1") (pintype "passive"))
      (node (ref "U$4") (pin "9") (pinfunction "SET_9") (pintype "bidirectional"))
    )
    (net (code "57") (name "Net-(U$6-COMP)") (class "Default")
      (node (ref "R13") (pin "2") (pinfunction "2_2") (pintype "passive"))
      (node (ref "U$6") (pin "3") (pinfunction "COMP_3") (pintype "bidirectional"))
    )
    (net (code "58") (name "Net-(U$6-EN)") (class "Default")
      (node (ref "C8") (pin "1") (pinfunction "1_1") (pintype "passive"))
      (node (ref "R21") (pin "1") (pinfunction "1_1") (pintype "passive"))
      (node (ref "U$6") (pin "2") (pinfunction "EN_2") (pintype "input"))
    )
    (net (code "59") (name "Net-(U$8-BYP)") (class "Default")
      (node (ref "C3") (pin "2") (pinfunction "2_2") (pintype "passive"))
      (node (ref "U$8") (pin "4") (pinfunction "BYP_4") (pintype "bidirectional"))
    )
    (net (code "60") (name "Net-(U2-ALERT)") (class "Default")
      (node (ref "U$1") (pin "31-CTX3") (pinfunction "31-CTX3_31-CTX3") (pintype "bidirectional"))
      (node (ref "U2") (pin "3") (pinfunction "ALERT_3") (pintype "output"))
    )
    (net (code "61") (name "Net-(U2-SCL)") (class "Default")
      (node (ref "R5") (pin "2") (pinfunction "2_2") (pintype "passive"))
      (node (ref "U$1") (pin "19-A5/SCL0") (pinfunction "19-A5/SCL0_19-A5/SCL0") (pintype "bidirectional"))
      (node (ref "U2") (pin "5") (pinfunction "SCL_5") (pintype "input"))
    )
    (net (code "62") (name "Net-(U2-SDA)") (class "Default")
      (node (ref "R2") (pin "2") (pinfunction "2_2") (pintype "passive"))
      (node (ref "U$1") (pin "18-A4/SDA0") (pinfunction "18-A4/SDA0_18-A4/SDA0") (pintype "bidirectional"))
      (node (ref "U2") (pin "4") (pinfunction "SDA_4") (pintype "bidirectional"))
    )
    (net (code "63") (name "unconnected-(K1-Pad3)") (class "Default")
      (node (ref "K1") (pin "3") (pinfunction "3_3") (pintype "passive"))
    )
    (net (code "64") (name "unconnected-(K1-Pad5)") (class "Default")
      (node (ref "K1") (pin "5") (pinfunction "5_5") (pintype "passive"))
    )
    (net (code "65") (name "unconnected-(K1-Pad8)") (class "Default")
      (node (ref "K1") (pin "8") (pinfunction "8_8") (pintype "passive"))
    )
    (net (code "66") (name "unconnected-(K1-Pad10)") (class "Default")
      (node (ref "K1") (pin "10") (pinfunction "10_10") (pintype "passive"))
    )
    (net (code "67") (name "unconnected-(K1-Pad12)") (class "Default")
      (node (ref "K1") (pin "12") (pinfunction "12_12") (pintype "passive"))
    )
    (net (code "68") (name "unconnected-(K1-Pad15)") (class "Default")
      (node (ref "K1") (pin "15") (pinfunction "15_15") (pintype "passive"))
    )
    (net (code "69") (name "unconnected-(K1-Pad16)") (class "Default")
      (node (ref "K1") (pin "16") (pinfunction "16_16") (pintype "passive"))
    )
    (net (code "70") (name "unconnected-(K1-Pad18)") (class "Default")
      (node (ref "K1") (pin "18") (pinfunction "18_18") (pintype "passive"))
    )
    (net (code "71") (name "unconnected-(K1-Pad21)") (class "Default")
      (node (ref "K1") (pin "21") (pinfunction "21_21") (pintype "passive"))
    )
    (net (code "72") (name "unconnected-(K1-Pad22)") (class "Default")
      (node (ref "K1") (pin "22") (pinfunction "22_22") (pintype "passive"))
    )
    (net (code "73") (name "unconnected-(K1-Pad24)") (class "Default")
      (node (ref "K1") (pin "24") (pinfunction "24_24") (pintype "passive"))
    )
    (net (code "74") (name "unconnected-(K1-Pad26)") (class "Default")
      (node (ref "K1") (pin "26") (pinfunction "26_26") (pintype "passive"))
    )
    (net (code "75") (name "unconnected-(K1-Pad27)") (class "Default")
      (node (ref "K1") (pin "27") (pinfunction "27_27") (pintype "passive"))
    )
    (net (code "76") (name "unconnected-(K1-Pad28)") (class "Default")
      (node (ref "K1") (pin "28") (pinfunction "28_28") (pintype "passive"))
    )
    (net (code "77") (name "unconnected-(K1-Pad31)") (class "Default")
      (node (ref "K1") (pin "31") (pinfunction "31_31") (pintype "passive"))
    )
    (net (code "78") (name "unconnected-(K1-Pad32)") (class "Default")
      (node (ref "K1") (pin "32") (pinfunction "32_32") (pintype "passive"))
    )
    (net (code "79") (name "unconnected-(K1-Pad33)") (class "Default")
      (node (ref "K1") (pin "33") (pinfunction "33_33") (pintype "passive"))
    )
    (net (code "80") (name "unconnected-(K1-Pad35)") (class "Default")
      (node (ref "K1") (pin "35") (pinfunction "35_35") (pintype "passive"))
    )
    (net (code "81") (name "unconnected-(K1-Pad36)") (class "Default")
      (node (ref "K1") (pin "36") (pinfunction "36_36") (pintype "passive"))
    )
    (net (code "82") (name "unconnected-(K1-Pad37)") (class "Default")
      (node (ref "K1") (pin "37") (pinfunction "37_37") (pintype "passive"))
    )
    (net (code "83") (name "unconnected-(K1-Pad38)") (class "Default")
      (node (ref "K1") (pin "38") (pinfunction "38_38") (pintype "passive"))
    )
    (net (code "84") (name "unconnected-(K1-Pad40)") (class "Default")
      (node (ref "K1") (pin "40") (pinfunction "40_40") (pintype "passive"))
    )
    (net (code "85") (name "unconnected-(U$1-5V-Pad+5V)") (class "Default")
      (node (ref "U$1") (pin "+5V") (pinfunction "5V_+5V") (pintype "bidirectional"))
    )
    (net (code "86") (name "unconnected-(U$1-10-CS{slash}MQSR-Pad10-CS\\MQSR)") (class "Default")
      (node (ref "U$1") (pin "10-CS\\MQSR") (pinfunction "10-CS/MQSR_10-CS\\MQSR") (pintype "bidirectional"))
    )
    (net (code "87") (name "unconnected-(U$1-Pad3V3-1)") (class "Default")
      (node (ref "U$1") (pin "3V3-1") (pinfunction "3V3-1_3V3-1") (pintype "bidirectional"))
    )
    (net (code "88") (name "unconnected-(U$1-Pad3V3-2)") (class "Default")
      (node (ref "U$1") (pin "3V3-2") (pinfunction "3V3-2_3V3-2") (pintype "bidirectional"))
    )
    (net (code "89") (name "unconnected-(U$1-Pad3V3-3)") (class "Default")
      (node (ref "U$1") (pin "3V3-3") (pinfunction "3V3-3_3V3-3") (pintype "bidirectional"))
    )
    (net (code "90") (name "unconnected-(U$1-Pad4-BCLK2)") (class "Default")
      (node (ref "U$1") (pin "4-BCLK2") (pinfunction "4-BCLK2_4-BCLK2") (pintype "bidirectional"))
    )
    (net (code "91") (name "unconnected-(U$1-Pad9-OUT1C)") (class "Default")
      (node (ref "U$1") (pin "9-OUT1C") (pinfunction "9-OUT1C_9-OUT1C") (pintype "bidirectional"))
    )
    (net (code "92") (name "unconnected-(U$1-Pad11-MOSI{slash}CTX1)") (class "Default")
      (node (ref "U$1") (pin "11-MOSI/CTX1") (pinfunction "11-MOSI/CTX1_11-MOSI/CTX1") (pintype "bidirectional"))
    )
    (net (code "93") (name "unconnected-(U$1-Pad12-MISO{slash}MQSL)") (class "Default")
      (node (ref "U$1") (pin "12-MISO/MQSL") (pinfunction "12-MISO/MQSL_12-MISO/MQSL") (pintype "bidirectional"))
    )
    (net (code "94") (name "unconnected-(U$1-Pad13-SCK{slash}LED)") (class "Default")
      (node (ref "U$1") (pin "13-SCK/LED") (pinfunction "13-SCK/LED_13-SCK/LED") (pintype "bidirectional"))
    )
    (net (code "95") (name "unconnected-(U$1-Pad26-A12{slash}MOSI1)") (class "Default")
      (node (ref "U$1") (pin "26-A12/MOSI1") (pinfunction "26-A12/MOSI1_26-A12/MOSI1") (pintype "bidirectional"))
    )
    (net (code "96") (name "unconnected-(U$1-Pad27-A13{slash}SCK1)") (class "Default")
      (node (ref "U$1") (pin "27-A13/SCK1") (pinfunction "27-A13/SCK1_27-A13/SCK1") (pintype "bidirectional"))
    )
    (net (code "97") (name "unconnected-(U$1-Pad36-PWM)") (class "Default")
      (node (ref "U$1") (pin "36-PWM") (pinfunction "36-PWM_36-PWM") (pintype "bidirectional"))
    )
    (net (code "98") (name "unconnected-(U$1-Pad37-PWM)") (class "Default")
      (node (ref "U$1") (pin "37-PWM") (pinfunction "37-PWM_37-PWM") (pintype "bidirectional"))
    )
    (net (code "99") (name "unconnected-(U$1-Pad40-A16{slash}CS1)") (class "Default")
      (node (ref "U$1") (pin "40-A16/CS1") (pinfunction "40-A16/CS1_40-A16/CS1") (pintype "bidirectional"))
    )
    (net (code "100") (name "unconnected-(U$1-Pad41-A17{slash}MISO1)") (class "Default")
      (node (ref "U$1") (pin "41-A17/MISO1") (pinfunction "41-A17/MISO1_41-A17/MISO1") (pintype "bidirectional"))
    )
    (net (code "101") (name "unconnected-(U$1-PadD+)") (class "Default")
      (node (ref "U$1") (pin "D+") (pinfunction "D+_D+") (pintype "bidirectional"))
    )
    (net (code "102") (name "unconnected-(U$1-PadD-)") (class "Default")
      (node (ref "U$1") (pin "D-") (pinfunction "D-_D-") (pintype "bidirectional"))
    )
    (net (code "103") (name "unconnected-(U$1-PadDM)") (class "Default")
      (node (ref "U$1") (pin "DM") (pinfunction "DM_DM") (pintype "bidirectional"))
    )
    (net (code "104") (name "unconnected-(U$1-PadDP)") (class "Default")
      (node (ref "U$1") (pin "DP") (pinfunction "DP_DP") (pintype "bidirectional"))
    )
    (net (code "105") (name "unconnected-(U$1-PadG)") (class "Default")
      (node (ref "U$1") (pin "G") (pinfunction "G_G") (pintype "bidirectional"))
    )
    (net (code "106") (name "unconnected-(U$1-PadLED)") (class "Default")
      (node (ref "U$1") (pin "LED") (pinfunction "LED_LED") (pintype "bidirectional"))
    )
    (net (code "107") (name "unconnected-(U$1-PadON{slash}OFF)") (class "Default")
      (node (ref "U$1") (pin "ON/OFF") (pinfunction "ON/OFF_ON/OFF") (pintype "bidirectional"))
    )
    (net (code "108") (name "unconnected-(U$1-PadPROGRAM)") (class "Default")
      (node (ref "U$1") (pin "PROGRAM") (pinfunction "PROGRAM_PROGRAM") (pintype "bidirectional"))
    )
    (net (code "109") (name "unconnected-(U$1-PadR+)") (class "Default")
      (node (ref "U$1") (pin "R+") (pinfunction "R+_R+") (pintype "bidirectional"))
    )
    (net (code "110") (name "unconnected-(U$1-PadR-)") (class "Default")
      (node (ref "U$1") (pin "R-") (pinfunction "R-_R-") (pintype "bidirectional"))
    )
    (net (code "111") (name "unconnected-(U$1-PadT+)") (class "Default")
      (node (ref "U$1") (pin "T+") (pinfunction "T+_T+") (pintype "bidirectional"))
    )
    (net (code "112") (name "unconnected-(U$1-PadT-)") (class "Default")
      (node (ref "U$1") (pin "T-") (pinfunction "T-_T-") (pintype "bidirectional"))
    )
    (net (code "113") (name "unconnected-(U$1-PadVBAT)") (class "Default")
      (node (ref "U$1") (pin "VBAT") (pinfunction "VBAT_VBAT") (pintype "bidirectional"))
    )
    (net (code "114") (name "unconnected-(U$1-PadVUSB)") (class "Default")
      (node (ref "U$1") (pin "VUSB") (pinfunction "VUSB_VUSB") (pintype "bidirectional"))
    )
    (net (code "115") (name "unconnected-(U$4-FAULT-Pad10)") (class "Default")
      (node (ref "U$4") (pin "10") (pinfunction "FAULT_10") (pintype "bidirectional"))
    )
  )
)
